# Radio_Module.net
KiCad netlist of a schematic drawn in EAGLE
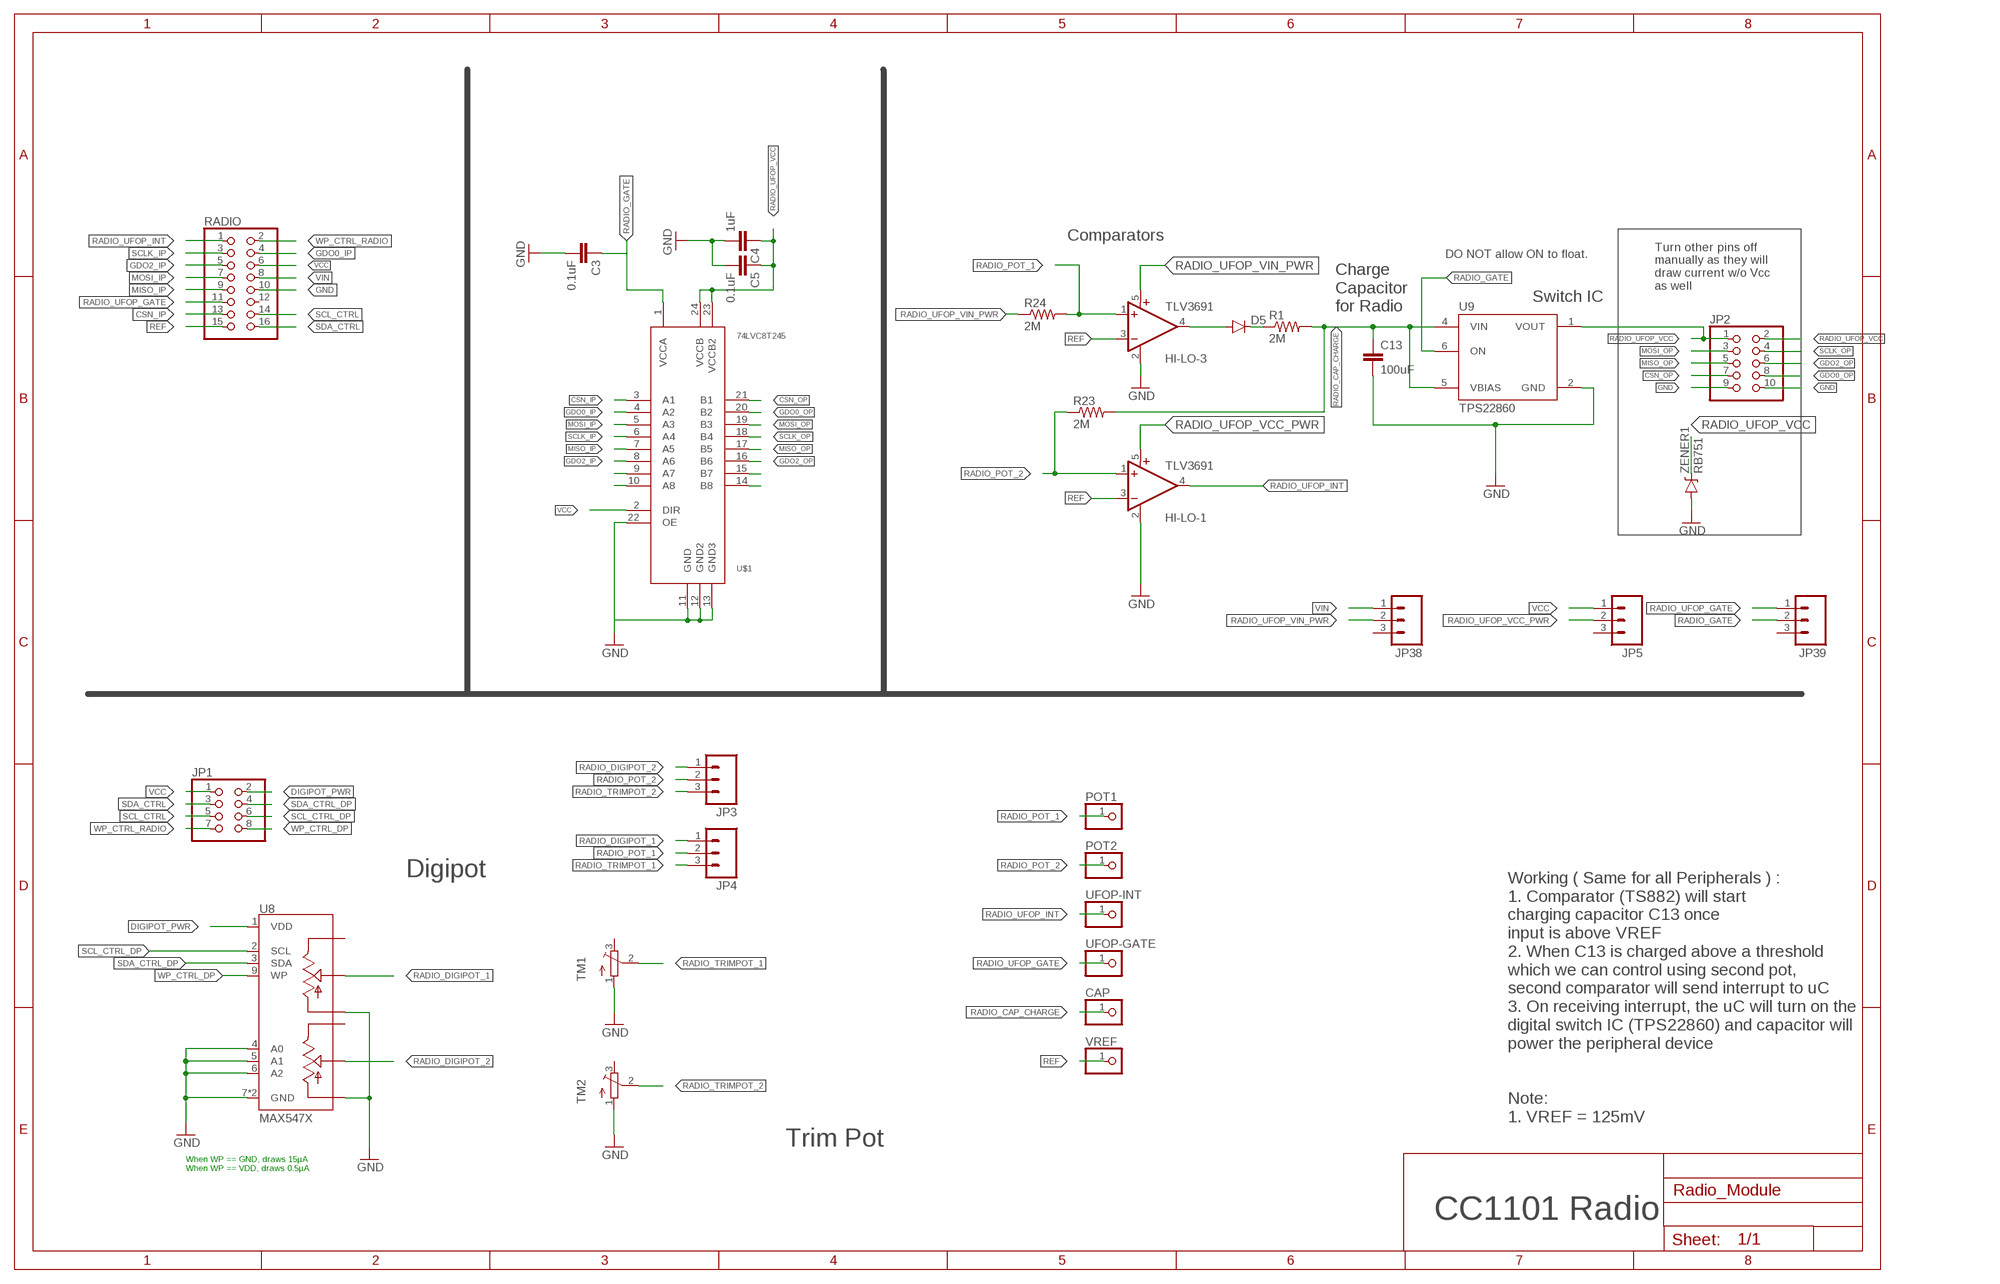
[diagram p0: schematic, sheet 1]

(export (version "E")
  (design (tool "Eeschema 10.0.6"))
  (components
    (comp (ref "C3")
      (value "0.1uF")
      (footprint "eagle-import:0805")
      (libsource (lib "eagle-import") (part "CAP0805"))
    )
    (comp (ref "C4")
      (value "1uF")
      (footprint "eagle-import:0805")
      (libsource (lib "eagle-import") (part "CAP0805"))
    )
    (comp (ref "C5")
      (value "0.1uF")
      (footprint "eagle-import:0805")
      (libsource (lib "eagle-import") (part "CAP0805"))
    )
    (comp (ref "C13")
      (value "100uF")
      (footprint "eagle-import:0805")
      (libsource (lib "eagle-import") (part "CAP0805"))
    )
    (comp (ref "CAP")
      (value "PINHD-1X1")
      (footprint "eagle-import:1X01")
      (libsource (lib "eagle-import") (part "PINHD-1X1"))
    )
    (comp (ref "D5")
      (value "DIODESOD523")
      (footprint "eagle-import:SOD523")
      (libsource (lib "eagle-import") (part "DIODESOD523"))
    )
    (comp (ref "HI-LO-1")
      (value "TLV3691")
      (footprint "eagle-import:SC70-5")
      (libsource (lib "eagle-import") (part "TLV3691"))
    )
    (comp (ref "HI-LO-3")
      (value "TLV3691")
      (footprint "eagle-import:SC70-5")
      (libsource (lib "eagle-import") (part "TLV3691"))
    )
    (comp (ref "JP1")
      (value "PINHD-2X4")
      (footprint "eagle-import:2X04")
      (libsource (lib "eagle-import") (part "PINHD-2X4"))
    )
    (comp (ref "JP2")
      (value "PINHD-2X5")
      (footprint "eagle-import:2X05")
      (libsource (lib "eagle-import") (part "PINHD-2X5"))
    )
    (comp (ref "JP3")
      (value "M03")
      (footprint "eagle-import:1X03-1.27MM")
      (libsource (lib "eagle-import") (part "M03"))
    )
    (comp (ref "JP4")
      (value "M03")
      (footprint "eagle-import:1X03-1.27MM")
      (libsource (lib "eagle-import") (part "M03"))
    )
    (comp (ref "JP5")
      (value "M03")
      (footprint "eagle-import:1X03-1.27MM")
      (libsource (lib "eagle-import") (part "M03"))
    )
    (comp (ref "JP38")
      (value "M03")
      (footprint "eagle-import:1X03-1.27MM")
      (libsource (lib "eagle-import") (part "M03"))
    )
    (comp (ref "JP39")
      (value "M03")
      (footprint "eagle-import:1X03-1.27MM")
      (libsource (lib "eagle-import") (part "M03"))
    )
    (comp (ref "POT1")
      (value "PINHD-1X1")
      (footprint "eagle-import:1X01")
      (libsource (lib "eagle-import") (part "PINHD-1X1"))
    )
    (comp (ref "POT2")
      (value "PINHD-1X1")
      (footprint "eagle-import:1X01")
      (libsource (lib "eagle-import") (part "PINHD-1X1"))
    )
    (comp (ref "R1")
      (value "2M")
      (footprint "eagle-import:0805")
      (libsource (lib "eagle-import") (part "RESISTOR0805-RES"))
    )
    (comp (ref "R23")
      (value "2M")
      (footprint "eagle-import:0805")
      (libsource (lib "eagle-import") (part "RESISTOR0805-RES"))
    )
    (comp (ref "R24")
      (value "2M")
      (footprint "eagle-import:0805")
      (libsource (lib "eagle-import") (part "RESISTOR0805-RES"))
    )
    (comp (ref "RADIO")
      (value "PINHD-2X8/90")
      (footprint "eagle-import:2X08_90")
      (libsource (lib "eagle-import") (part "PINHD-2X8/90"))
    )
    (comp (ref "TM1")
      (value "TRIMPOTTC33X")
      (footprint "eagle-import:TC33X")
      (libsource (lib "eagle-import") (part "TRIMPOTTC33X"))
    )
    (comp (ref "TM2")
      (value "TRIMPOTTC33X")
      (footprint "eagle-import:TC33X")
      (libsource (lib "eagle-import") (part "TRIMPOTTC33X"))
    )
    (comp (ref "U$1")
      (value "74LVC8T245")
      (footprint "eagle-import:TSSOP24")
      (libsource (lib "eagle-import") (part "74LVC8T245"))
    )
    (comp (ref "U8")
      (value "MAX547X")
      (footprint "eagle-import:QFN16")
      (libsource (lib "eagle-import") (part "MAX547X"))
    )
    (comp (ref "U9")
      (value "TPS22860")
      (footprint "eagle-import:TSOT23-6")
      (libsource (lib "eagle-import") (part "TPS22860"))
    )
    (comp (ref "UFOP-GATE")
      (value "PINHD-1X1")
      (footprint "eagle-import:1X01")
      (libsource (lib "eagle-import") (part "PINHD-1X1"))
    )
    (comp (ref "UFOP-INT")
      (value "PINHD-1X1")
      (footprint "eagle-import:1X01")
      (libsource (lib "eagle-import") (part "PINHD-1X1"))
    )
    (comp (ref "VREF")
      (value "PINHD-1X1")
      (footprint "eagle-import:1X01")
      (libsource (lib "eagle-import") (part "PINHD-1X1"))
    )
    (comp (ref "ZENER1")
      (value "RB751")
      (footprint "eagle-import:SOD-523")
      (libsource (lib "eagle-import") (part "DIODE-ZENER"))
    )
  )
  (nets
    (net (code "1") (name "CSN_IP") (class "Default")
      (node (ref "RADIO") (pin "13") (pinfunction "13_13") (pintype "passive"))
      (node (ref "U$1") (pin "3") (pinfunction "A1_3") (pintype "bidirectional"))
    )
    (net (code "2") (name "CSN_OP") (class "Default")
      (node (ref "JP2") (pin "7") (pinfunction "7_7") (pintype "passive"))
      (node (ref "U$1") (pin "21") (pinfunction "B1_21") (pintype "bidirectional"))
    )
    (net (code "3") (name "DIGIPOT_PWR") (class "Default")
      (node (ref "JP1") (pin "2") (pinfunction "2_2") (pintype "passive"))
      (node (ref "U8") (pin "1") (pinfunction "VDD_1") (pintype "bidirectional"))
    )
    (net (code "4") (name "GDO0_IP") (class "Default")
      (node (ref "RADIO") (pin "4") (pinfunction "4_4") (pintype "passive"))
      (node (ref "U$1") (pin "4") (pinfunction "A2_4") (pintype "bidirectional"))
    )
    (net (code "5") (name "GDO0_OP") (class "Default")
      (node (ref "JP2") (pin "8") (pinfunction "8_8") (pintype "passive"))
      (node (ref "U$1") (pin "20") (pinfunction "B2_20") (pintype "bidirectional"))
    )
    (net (code "6") (name "GDO2_IP") (class "Default")
      (node (ref "RADIO") (pin "5") (pinfunction "5_5") (pintype "passive"))
      (node (ref "U$1") (pin "8") (pinfunction "A6_8") (pintype "bidirectional"))
    )
    (net (code "7") (name "GDO2_OP") (class "Default")
      (node (ref "JP2") (pin "6") (pinfunction "6_6") (pintype "passive"))
      (node (ref "U$1") (pin "16") (pinfunction "B6_16") (pintype "bidirectional"))
    )
    (net (code "8") (name "GND") (class "Default")
      (node (ref "C13") (pin "2") (pinfunction "2_2") (pintype "passive"))
      (node (ref "C3") (pin "2") (pinfunction "2_2") (pintype "passive"))
      (node (ref "C4") (pin "2") (pinfunction "2_2") (pintype "passive"))
      (node (ref "C5") (pin "2") (pinfunction "2_2") (pintype "passive"))
      (node (ref "HI-LO-1") (pin "2") (pinfunction "GND_2") (pintype "power_in"))
      (node (ref "HI-LO-3") (pin "2") (pinfunction "GND_2") (pintype "power_in"))
      (node (ref "JP2") (pin "10") (pinfunction "10_10") (pintype "passive"))
      (node (ref "JP2") (pin "9") (pinfunction "9_9") (pintype "passive"))
      (node (ref "RADIO") (pin "10") (pinfunction "10_10") (pintype "passive"))
      (node (ref "TM1") (pin "1") (pinfunction "A_1") (pintype "passive"))
      (node (ref "TM2") (pin "1") (pinfunction "A_1") (pintype "passive"))
      (node (ref "U$1") (pin "11") (pinfunction "GND_11") (pintype "bidirectional"))
      (node (ref "U$1") (pin "12") (pinfunction "GND2_12") (pintype "bidirectional"))
      (node (ref "U$1") (pin "13") (pinfunction "GND3_13") (pintype "bidirectional"))
      (node (ref "U$1") (pin "22") (pinfunction "OE_22") (pintype "bidirectional"))
      (node (ref "U8") (pin "10") (pinfunction "LB_10") (pintype "bidirectional"))
      (node (ref "U8") (pin "13") (pinfunction "LA_13") (pintype "passive"))
      (node (ref "U8") (pin "4") (pinfunction "A0_4") (pintype "bidirectional"))
      (node (ref "U8") (pin "5") (pinfunction "A1_5") (pintype "bidirectional"))
      (node (ref "U8") (pin "6") (pinfunction "A2_6") (pintype "bidirectional"))
      (node (ref "U8") (pin "7") (pinfunction "GND_7") (pintype "bidirectional"))
      (node (ref "U8") (pin "TH") (pinfunction "GND_TH") (pintype "bidirectional"))
      (node (ref "U9") (pin "2") (pinfunction "GND_2") (pintype "bidirectional"))
      (node (ref "ZENER1") (pin "ANODE") (pinfunction "A_ANODE") (pintype "passive"))
    )
    (net (code "9") (name "MISO_IP") (class "Default")
      (node (ref "RADIO") (pin "9") (pinfunction "9_9") (pintype "passive"))
      (node (ref "U$1") (pin "7") (pinfunction "A5_7") (pintype "bidirectional"))
    )
    (net (code "10") (name "MISO_OP") (class "Default")
      (node (ref "JP2") (pin "5") (pinfunction "5_5") (pintype "passive"))
      (node (ref "U$1") (pin "17") (pinfunction "B5_17") (pintype "bidirectional"))
    )
    (net (code "11") (name "MOSI_IP") (class "Default")
      (node (ref "RADIO") (pin "7") (pinfunction "7_7") (pintype "passive"))
      (node (ref "U$1") (pin "5") (pinfunction "A3_5") (pintype "bidirectional"))
    )
    (net (code "12") (name "MOSI_OP") (class "Default")
      (node (ref "JP2") (pin "3") (pinfunction "3_3") (pintype "passive"))
      (node (ref "U$1") (pin "19") (pinfunction "B3_19") (pintype "bidirectional"))
    )
    (net (code "13") (name "Net-(D5-PadC)") (class "Default")
      (node (ref "D5") (pin "C") (pinfunction "C_C") (pintype "passive"))
      (node (ref "R1") (pin "1") (pinfunction "1_1") (pintype "passive"))
    )
    (net (code "14") (name "Net-(HI-LO-3-OUT)") (class "Default")
      (node (ref "D5") (pin "A") (pinfunction "A_A") (pintype "passive"))
      (node (ref "HI-LO-3") (pin "4") (pinfunction "OUT_4") (pintype "output"))
    )
    (net (code "15") (name "RADIO_CAP_CHARGE") (class "Default")
      (node (ref "C13") (pin "1") (pinfunction "1_1") (pintype "passive"))
      (node (ref "CAP") (pin "1") (pinfunction "1_1") (pintype "passive"))
      (node (ref "R1") (pin "2") (pinfunction "2_2") (pintype "passive"))
      (node (ref "R23") (pin "2") (pinfunction "2_2") (pintype "passive"))
      (node (ref "U9") (pin "4") (pinfunction "VIN_4") (pintype "bidirectional"))
      (node (ref "U9") (pin "5") (pinfunction "VBIAS_5") (pintype "bidirectional"))
    )
    (net (code "16") (name "RADIO_DIGIPOT_1") (class "Default")
      (node (ref "JP4") (pin "1") (pinfunction "1_1") (pintype "passive"))
      (node (ref "U8") (pin "14") (pinfunction "WA_14") (pintype "passive"))
    )
    (net (code "17") (name "RADIO_DIGIPOT_2") (class "Default")
      (node (ref "JP3") (pin "1") (pinfunction "1_1") (pintype "passive"))
      (node (ref "U8") (pin "11") (pinfunction "WB_11") (pintype "bidirectional"))
    )
    (net (code "18") (name "RADIO_GATE") (class "Default")
      (node (ref "C3") (pin "1") (pinfunction "1_1") (pintype "passive"))
      (node (ref "JP39") (pin "2") (pinfunction "2_2") (pintype "passive"))
      (node (ref "U$1") (pin "1") (pinfunction "VCCA_1") (pintype "bidirectional"))
      (node (ref "U9") (pin "6") (pinfunction "ON_6") (pintype "bidirectional"))
    )
    (net (code "19") (name "RADIO_POT_1") (class "Default")
      (node (ref "HI-LO-3") (pin "1") (pinfunction "+IN_1") (pintype "input"))
      (node (ref "JP4") (pin "2") (pinfunction "2_2") (pintype "passive"))
      (node (ref "POT1") (pin "1") (pinfunction "1_1") (pintype "passive"))
      (node (ref "R24") (pin "2") (pinfunction "2_2") (pintype "passive"))
    )
    (net (code "20") (name "RADIO_POT_2") (class "Default")
      (node (ref "HI-LO-1") (pin "1") (pinfunction "+IN_1") (pintype "input"))
      (node (ref "JP3") (pin "2") (pinfunction "2_2") (pintype "passive"))
      (node (ref "POT2") (pin "1") (pinfunction "1_1") (pintype "passive"))
      (node (ref "R23") (pin "1") (pinfunction "1_1") (pintype "passive"))
    )
    (net (code "21") (name "RADIO_TRIMPOT_1") (class "Default")
      (node (ref "JP4") (pin "3") (pinfunction "3_3") (pintype "passive"))
      (node (ref "TM1") (pin "2") (pinfunction "S_2") (pintype "passive"))
    )
    (net (code "22") (name "RADIO_TRIMPOT_2") (class "Default")
      (node (ref "JP3") (pin "3") (pinfunction "3_3") (pintype "passive"))
      (node (ref "TM2") (pin "2") (pinfunction "S_2") (pintype "passive"))
    )
    (net (code "23") (name "RADIO_UFOP_GATE") (class "Default")
      (node (ref "JP39") (pin "1") (pinfunction "1_1") (pintype "passive"))
      (node (ref "RADIO") (pin "11") (pinfunction "11_11") (pintype "passive"))
      (node (ref "UFOP-GATE") (pin "1") (pinfunction "1_1") (pintype "passive"))
    )
    (net (code "24") (name "RADIO_UFOP_INT") (class "Default")
      (node (ref "HI-LO-1") (pin "4") (pinfunction "OUT_4") (pintype "output"))
      (node (ref "RADIO") (pin "1") (pinfunction "1_1") (pintype "passive"))
      (node (ref "UFOP-INT") (pin "1") (pinfunction "1_1") (pintype "passive"))
    )
    (net (code "25") (name "RADIO_UFOP_VCC") (class "Default")
      (node (ref "C4") (pin "1") (pinfunction "1_1") (pintype "passive"))
      (node (ref "C5") (pin "1") (pinfunction "1_1") (pintype "passive"))
      (node (ref "JP2") (pin "1") (pinfunction "1_1") (pintype "passive"))
      (node (ref "JP2") (pin "2") (pinfunction "2_2") (pintype "passive"))
      (node (ref "U$1") (pin "23") (pinfunction "VCCB2_23") (pintype "bidirectional"))
      (node (ref "U$1") (pin "24") (pinfunction "VCCB_24") (pintype "bidirectional"))
      (node (ref "U9") (pin "1") (pinfunction "VOUT_1") (pintype "bidirectional"))
      (node (ref "ZENER1") (pin "CATHODE") (pinfunction "C_CATHODE") (pintype "passive"))
    )
    (net (code "26") (name "RADIO_UFOP_VCC_PWR") (class "Default")
      (node (ref "HI-LO-1") (pin "5") (pinfunction "V+_5") (pintype "power_in"))
      (node (ref "JP5") (pin "2") (pinfunction "2_2") (pintype "passive"))
    )
    (net (code "27") (name "RADIO_UFOP_VIN_PWR") (class "Default")
      (node (ref "HI-LO-3") (pin "5") (pinfunction "V+_5") (pintype "power_in"))
      (node (ref "JP38") (pin "2") (pinfunction "2_2") (pintype "passive"))
      (node (ref "R24") (pin "1") (pinfunction "1_1") (pintype "passive"))
    )
    (net (code "28") (name "REF") (class "Default")
      (node (ref "HI-LO-1") (pin "3") (pinfunction "-IN_3") (pintype "input"))
      (node (ref "HI-LO-3") (pin "3") (pinfunction "-IN_3") (pintype "input"))
      (node (ref "RADIO") (pin "15") (pinfunction "15_15") (pintype "passive"))
      (node (ref "VREF") (pin "1") (pinfunction "1_1") (pintype "passive"))
    )
    (net (code "29") (name "SCLK_IP") (class "Default")
      (node (ref "RADIO") (pin "3") (pinfunction "3_3") (pintype "passive"))
      (node (ref "U$1") (pin "6") (pinfunction "A4_6") (pintype "bidirectional"))
    )
    (net (code "30") (name "SCLK_OP") (class "Default")
      (node (ref "JP2") (pin "4") (pinfunction "4_4") (pintype "passive"))
      (node (ref "U$1") (pin "18") (pinfunction "B4_18") (pintype "bidirectional"))
    )
    (net (code "31") (name "SCL_CTRL") (class "Default")
      (node (ref "JP1") (pin "5") (pinfunction "5_5") (pintype "passive"))
      (node (ref "RADIO") (pin "14") (pinfunction "14_14") (pintype "passive"))
    )
    (net (code "32") (name "SCL_CTRL_DP") (class "Default")
      (node (ref "JP1") (pin "6") (pinfunction "6_6") (pintype "passive"))
      (node (ref "U8") (pin "2") (pinfunction "SCL_2") (pintype "bidirectional"))
    )
    (net (code "33") (name "SDA_CTRL") (class "Default")
      (node (ref "JP1") (pin "3") (pinfunction "3_3") (pintype "passive"))
      (node (ref "RADIO") (pin "16") (pinfunction "16_16") (pintype "passive"))
    )
    (net (code "34") (name "SDA_CTRL_DP") (class "Default")
      (node (ref "JP1") (pin "4") (pinfunction "4_4") (pintype "passive"))
      (node (ref "U8") (pin "3") (pinfunction "SDA_3") (pintype "bidirectional"))
    )
    (net (code "35") (name "VCC") (class "Default")
      (node (ref "JP1") (pin "1") (pinfunction "1_1") (pintype "passive"))
      (node (ref "JP5") (pin "1") (pinfunction "1_1") (pintype "passive"))
      (node (ref "RADIO") (pin "6") (pinfunction "6_6") (pintype "passive"))
      (node (ref "U$1") (pin "2") (pinfunction "DIR_2") (pintype "bidirectional"))
    )
    (net (code "36") (name "VIN") (class "Default")
      (node (ref "JP38") (pin "1") (pinfunction "1_1") (pintype "passive"))
      (node (ref "RADIO") (pin "8") (pinfunction "8_8") (pintype "passive"))
    )
    (net (code "37") (name "WP_CTRL_DP") (class "Default")
      (node (ref "JP1") (pin "8") (pinfunction "8_8") (pintype "passive"))
      (node (ref "U8") (pin "9") (pinfunction "WP_9") (pintype "bidirectional"))
    )
    (net (code "38") (name "WP_CTRL_RADIO") (class "Default")
      (node (ref "JP1") (pin "7") (pinfunction "7_7") (pintype "passive"))
      (node (ref "RADIO") (pin "2") (pinfunction "2_2") (pintype "passive"))
    )
    (net (code "39") (name "unconnected-(JP5-Pad3)") (class "Default")
      (node (ref "JP5") (pin "3") (pinfunction "3_3") (pintype "passive"))
    )
    (net (code "40") (name "unconnected-(JP38-Pad3)") (class "Default")
      (node (ref "JP38") (pin "3") (pinfunction "3_3") (pintype "passive"))
    )
    (net (code "41") (name "unconnected-(JP39-Pad3)") (class "Default")
      (node (ref "JP39") (pin "3") (pinfunction "3_3") (pintype "passive"))
    )
    (net (code "42") (name "unconnected-(RADIO-Pad12)") (class "Default")
      (node (ref "RADIO") (pin "12") (pinfunction "12_12") (pintype "passive"))
    )
    (net (code "43") (name "unconnected-(TM1-E-Pad3)") (class "Default")
      (node (ref "TM1") (pin "3") (pinfunction "E_3") (pintype "passive"))
    )
    (net (code "44") (name "unconnected-(TM2-E-Pad3)") (class "Default")
      (node (ref "TM2") (pin "3") (pinfunction "E_3") (pintype "passive"))
    )
    (net (code "45") (name "unconnected-(U$1-A7-Pad9)") (class "Default")
      (node (ref "U$1") (pin "9") (pinfunction "A7_9") (pintype "bidirectional"))
    )
    (net (code "46") (name "unconnected-(U$1-A8-Pad10)") (class "Default")
      (node (ref "U$1") (pin "10") (pinfunction "A8_10") (pintype "bidirectional"))
    )
    (net (code "47") (name "unconnected-(U$1-B7-Pad15)") (class "Default")
      (node (ref "U$1") (pin "15") (pinfunction "B7_15") (pintype "bidirectional"))
    )
    (net (code "48") (name "unconnected-(U$1-B8-Pad14)") (class "Default")
      (node (ref "U$1") (pin "14") (pinfunction "B8_14") (pintype "bidirectional"))
    )
    (net (code "49") (name "unconnected-(U8-HA-Pad15)") (class "Default")
      (node (ref "U8") (pin "15") (pinfunction "HA_15") (pintype "passive"))
    )
    (net (code "50") (name "unconnected-(U8-HB-Pad12)") (class "Default")
      (node (ref "U8") (pin "12") (pinfunction "HB_12") (pintype "bidirectional"))
    )
  )
)
